# TeamFlag.net
KiCad netlist of a schematic drawn in EAGLE
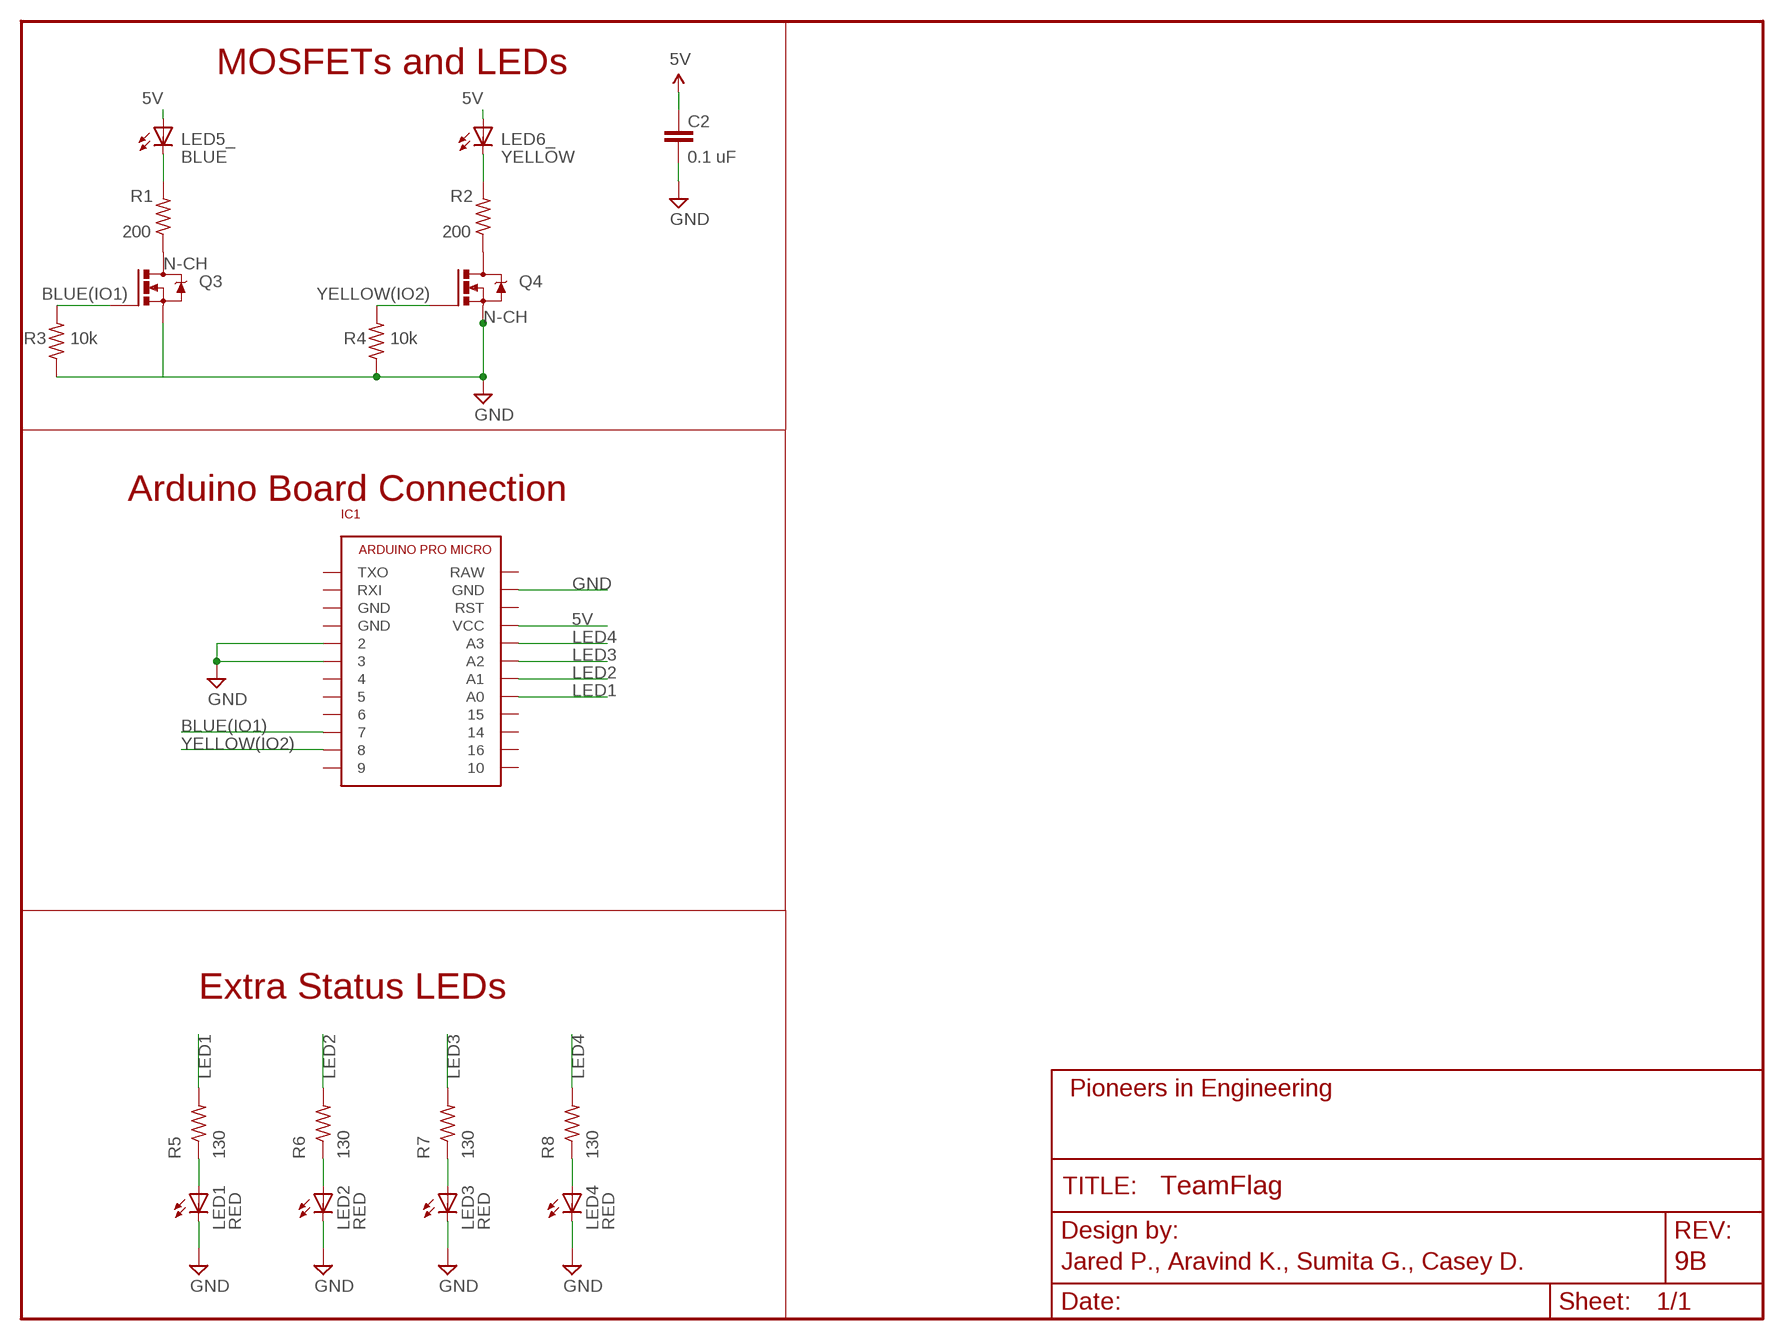
[diagram p0: schematic, sheet 1]

(export (version "E")
  (design (tool "Eeschema 10.0.6"))
  (components
    (comp (ref "C2")
      (value "0.1 uF")
      (footprint "eagle-import:0603-CAP")
      (libsource (lib "eagle-import") (part "CAP0603-CAP"))
    )
    (comp (ref "IC1")
      (value "ARDUINO_PRO_MICROSMD")
      (footprint "eagle-import:ARDUINO_PRO_MICRO_SM")
      (libsource (lib "eagle-import") (part "ARDUINO_PRO_MICROSMD"))
    )
    (comp (ref "LED1")
      (value "RED")
      (footprint "eagle-import:LED-0805")
      (libsource (lib "eagle-import") (part "LED0805"))
    )
    (comp (ref "LED2")
      (value "RED")
      (footprint "eagle-import:LED-0805")
      (libsource (lib "eagle-import") (part "LED0805"))
    )
    (comp (ref "LED3")
      (value "RED")
      (footprint "eagle-import:LED-0805")
      (libsource (lib "eagle-import") (part "LED0805"))
    )
    (comp (ref "LED4")
      (value "RED")
      (footprint "eagle-import:LED-0805")
      (libsource (lib "eagle-import") (part "LED0805"))
    )
    (comp (ref "LED5_")
      (value "BLUE")
      (footprint "eagle-import:LED5MM-NOFLAT")
      (libsource (lib "eagle-import") (part "LEDLED5MM-NOFLAT"))
    )
    (comp (ref "LED6_")
      (value "YELLOW")
      (footprint "eagle-import:LED5MM-NOFLAT")
      (libsource (lib "eagle-import") (part "LEDLED5MM-NOFLAT"))
    )
    (comp (ref "Q3")
      (value "N-CH")
      (footprint "eagle-import:SOT23-3")
      (libsource (lib "eagle-import") (part "N-CHANNEL-MOSFETSOT23-3"))
    )
    (comp (ref "Q4")
      (value "N-CH")
      (footprint "eagle-import:SOT23-3")
      (libsource (lib "eagle-import") (part "N-CHANNEL-MOSFETSOT23-3"))
    )
    (comp (ref "R1")
      (value "200")
      (footprint "eagle-import:R0603")
      (fields (field (name "MANUFACTURER") "Rohm Semiconductor"))
      (libsource (lib "eagle-import") (part "R-US_R0603"))
    )
    (comp (ref "R2")
      (value "200")
      (footprint "eagle-import:R0603")
      (fields (field (name "MANUFACTURER") "Rohm Semiconductor"))
      (libsource (lib "eagle-import") (part "R-US_R0603"))
    )
    (comp (ref "R3")
      (value "10k")
      (footprint "eagle-import:R0603")
      (fields (field (name "MANUFACTURER") "Rohm Semiconductor"))
      (libsource (lib "eagle-import") (part "R-US_R0603"))
    )
    (comp (ref "R4")
      (value "10k")
      (footprint "eagle-import:R0603")
      (fields (field (name "MANUFACTURER") "Rohm Semiconductor"))
      (libsource (lib "eagle-import") (part "R-US_R0603"))
    )
    (comp (ref "R5")
      (value "130")
      (footprint "eagle-import:R0603")
      (fields (field (name "MANUFACTURER") "Rohm Semiconductor"))
      (libsource (lib "eagle-import") (part "R-US_R0603"))
    )
    (comp (ref "R6")
      (value "130")
      (footprint "eagle-import:R0603")
      (fields (field (name "MANUFACTURER") "Rohm Semiconductor"))
      (libsource (lib "eagle-import") (part "R-US_R0603"))
    )
    (comp (ref "R7")
      (value "130")
      (footprint "eagle-import:R0603")
      (fields (field (name "MANUFACTURER") "Rohm Semiconductor"))
      (libsource (lib "eagle-import") (part "R-US_R0603"))
    )
    (comp (ref "R8")
      (value "130")
      (footprint "eagle-import:R0603")
      (fields (field (name "MANUFACTURER") "Rohm Semiconductor"))
      (libsource (lib "eagle-import") (part "R-US_R0603"))
    )
  )
  (nets
    (net (code "1") (name "/BLUE(IO1)") (class "Default")
      (node (ref "IC1") (pin "7") (pinfunction "7_7") (pintype "bidirectional"))
      (node (ref "Q3") (pin "1") (pinfunction "G_1") (pintype "passive"))
      (node (ref "R3") (pin "2") (pinfunction "2_2") (pintype "passive"))
    )
    (net (code "2") (name "/LED1") (class "Default")
      (node (ref "IC1") (pin "A0") (pinfunction "A0_A0") (pintype "bidirectional"))
      (node (ref "R5") (pin "2") (pinfunction "2_2") (pintype "passive"))
    )
    (net (code "3") (name "/LED2") (class "Default")
      (node (ref "IC1") (pin "A1") (pinfunction "A1_A1") (pintype "bidirectional"))
      (node (ref "R6") (pin "2") (pinfunction "2_2") (pintype "passive"))
    )
    (net (code "4") (name "/LED3") (class "Default")
      (node (ref "IC1") (pin "A2") (pinfunction "A2_A2") (pintype "bidirectional"))
      (node (ref "R7") (pin "2") (pinfunction "2_2") (pintype "passive"))
    )
    (net (code "5") (name "/LED4") (class "Default")
      (node (ref "IC1") (pin "A3") (pinfunction "A3_A3") (pintype "bidirectional"))
      (node (ref "R8") (pin "2") (pinfunction "2_2") (pintype "passive"))
    )
    (net (code "6") (name "/YELLOW(IO2)") (class "Default")
      (node (ref "IC1") (pin "8") (pinfunction "8_8") (pintype "bidirectional"))
      (node (ref "Q4") (pin "1") (pinfunction "G_1") (pintype "passive"))
      (node (ref "R4") (pin "2") (pinfunction "2_2") (pintype "passive"))
    )
    (net (code "7") (name "5V") (class "Default")
      (node (ref "C2") (pin "1") (pinfunction "1_1") (pintype "passive"))
      (node (ref "IC1") (pin "VCC") (pinfunction "VCC_VCC") (pintype "bidirectional"))
      (node (ref "LED5_") (pin "A") (pinfunction "A_A") (pintype "passive"))
      (node (ref "LED6_") (pin "A") (pinfunction "A_A") (pintype "passive"))
    )
    (net (code "8") (name "GND") (class "Default")
      (node (ref "C2") (pin "2") (pinfunction "2_2") (pintype "passive"))
      (node (ref "IC1") (pin "2") (pinfunction "2_2") (pintype "bidirectional"))
      (node (ref "IC1") (pin "3") (pinfunction "3_3") (pintype "bidirectional"))
      (node (ref "IC1") (pin "GND@2") (pinfunction "GND_GND@2") (pintype "bidirectional"))
      (node (ref "LED1") (pin "C") (pinfunction "C_C") (pintype "passive"))
      (node (ref "LED2") (pin "C") (pinfunction "C_C") (pintype "passive"))
      (node (ref "LED3") (pin "C") (pinfunction "C_C") (pintype "passive"))
      (node (ref "LED4") (pin "C") (pinfunction "C_C") (pintype "passive"))
      (node (ref "Q3") (pin "2") (pinfunction "S_2") (pintype "passive"))
      (node (ref "Q4") (pin "2") (pinfunction "S_2") (pintype "passive"))
      (node (ref "R3") (pin "1") (pinfunction "1_1") (pintype "passive"))
      (node (ref "R4") (pin "1") (pinfunction "1_1") (pintype "passive"))
    )
    (net (code "9") (name "Net-(LED1-PadA)") (class "Default")
      (node (ref "LED1") (pin "A") (pinfunction "A_A") (pintype "passive"))
      (node (ref "R5") (pin "1") (pinfunction "1_1") (pintype "passive"))
    )
    (net (code "10") (name "Net-(LED2-PadA)") (class "Default")
      (node (ref "LED2") (pin "A") (pinfunction "A_A") (pintype "passive"))
      (node (ref "R6") (pin "1") (pinfunction "1_1") (pintype "passive"))
    )
    (net (code "11") (name "Net-(LED3-PadA)") (class "Default")
      (node (ref "LED3") (pin "A") (pinfunction "A_A") (pintype "passive"))
      (node (ref "R7") (pin "1") (pinfunction "1_1") (pintype "passive"))
    )
    (net (code "12") (name "Net-(LED4-PadA)") (class "Default")
      (node (ref "LED4") (pin "A") (pinfunction "A_A") (pintype "passive"))
      (node (ref "R8") (pin "1") (pinfunction "1_1") (pintype "passive"))
    )
    (net (code "13") (name "Net-(LED5_-C)") (class "Default")
      (node (ref "LED5_") (pin "K") (pinfunction "C_K") (pintype "passive"))
      (node (ref "R1") (pin "2") (pinfunction "2_2") (pintype "passive"))
    )
    (net (code "14") (name "Net-(LED6_-C)") (class "Default")
      (node (ref "LED6_") (pin "K") (pinfunction "C_K") (pintype "passive"))
      (node (ref "R2") (pin "2") (pinfunction "2_2") (pintype "passive"))
    )
    (net (code "15") (name "Net-(Q3-D)") (class "Default")
      (node (ref "Q3") (pin "3") (pinfunction "D_3") (pintype "passive"))
      (node (ref "R1") (pin "1") (pinfunction "1_1") (pintype "passive"))
    )
    (net (code "16") (name "Net-(Q4-D)") (class "Default")
      (node (ref "Q4") (pin "3") (pinfunction "D_3") (pintype "passive"))
      (node (ref "R2") (pin "1") (pinfunction "1_1") (pintype "passive"))
    )
    (net (code "17") (name "unconnected-(IC1-GND-PadGND@1)") (class "Default")
      (node (ref "IC1") (pin "GND@1") (pinfunction "GND_GND@1") (pintype "bidirectional"))
    )
    (net (code "18") (name "unconnected-(IC1-Pad4)") (class "Default")
      (node (ref "IC1") (pin "4") (pinfunction "4_4") (pintype "bidirectional"))
    )
    (net (code "19") (name "unconnected-(IC1-Pad5)") (class "Default")
      (node (ref "IC1") (pin "5") (pinfunction "5_5") (pintype "bidirectional"))
    )
    (net (code "20") (name "unconnected-(IC1-Pad6)") (class "Default")
      (node (ref "IC1") (pin "6") (pinfunction "6_6") (pintype "bidirectional"))
    )
    (net (code "21") (name "unconnected-(IC1-Pad9)") (class "Default")
      (node (ref "IC1") (pin "9") (pinfunction "9_9") (pintype "bidirectional"))
    )
    (net (code "22") (name "unconnected-(IC1-Pad10)") (class "Default")
      (node (ref "IC1") (pin "10") (pinfunction "10_10") (pintype "bidirectional"))
    )
    (net (code "23") (name "unconnected-(IC1-Pad14)") (class "Default")
      (node (ref "IC1") (pin "14") (pinfunction "14_14") (pintype "bidirectional"))
    )
    (net (code "24") (name "unconnected-(IC1-Pad15)") (class "Default")
      (node (ref "IC1") (pin "15") (pinfunction "15_15") (pintype "bidirectional"))
    )
    (net (code "25") (name "unconnected-(IC1-Pad16)") (class "Default")
      (node (ref "IC1") (pin "16") (pinfunction "16_16") (pintype "bidirectional"))
    )
    (net (code "26") (name "unconnected-(IC1-PadGND)") (class "Default")
      (node (ref "IC1") (pin "GND") (pinfunction "GND_GND") (pintype "bidirectional"))
    )
    (net (code "27") (name "unconnected-(IC1-PadRAW)") (class "Default")
      (node (ref "IC1") (pin "RAW") (pinfunction "RAW_RAW") (pintype "bidirectional"))
    )
    (net (code "28") (name "unconnected-(IC1-PadRST)") (class "Default")
      (node (ref "IC1") (pin "RST") (pinfunction "RST_RST") (pintype "bidirectional"))
    )
    (net (code "29") (name "unconnected-(IC1-RXI-PadRX)") (class "Default")
      (node (ref "IC1") (pin "RX") (pinfunction "RXI_RX") (pintype "bidirectional"))
    )
    (net (code "30") (name "unconnected-(IC1-TXO-PadTX)") (class "Default")
      (node (ref "IC1") (pin "TX") (pinfunction "TXO_TX") (pintype "bidirectional"))
    )
  )
)
